# FeatherBigLatchingRelay.net
KiCad netlist of a schematic drawn in EAGLE
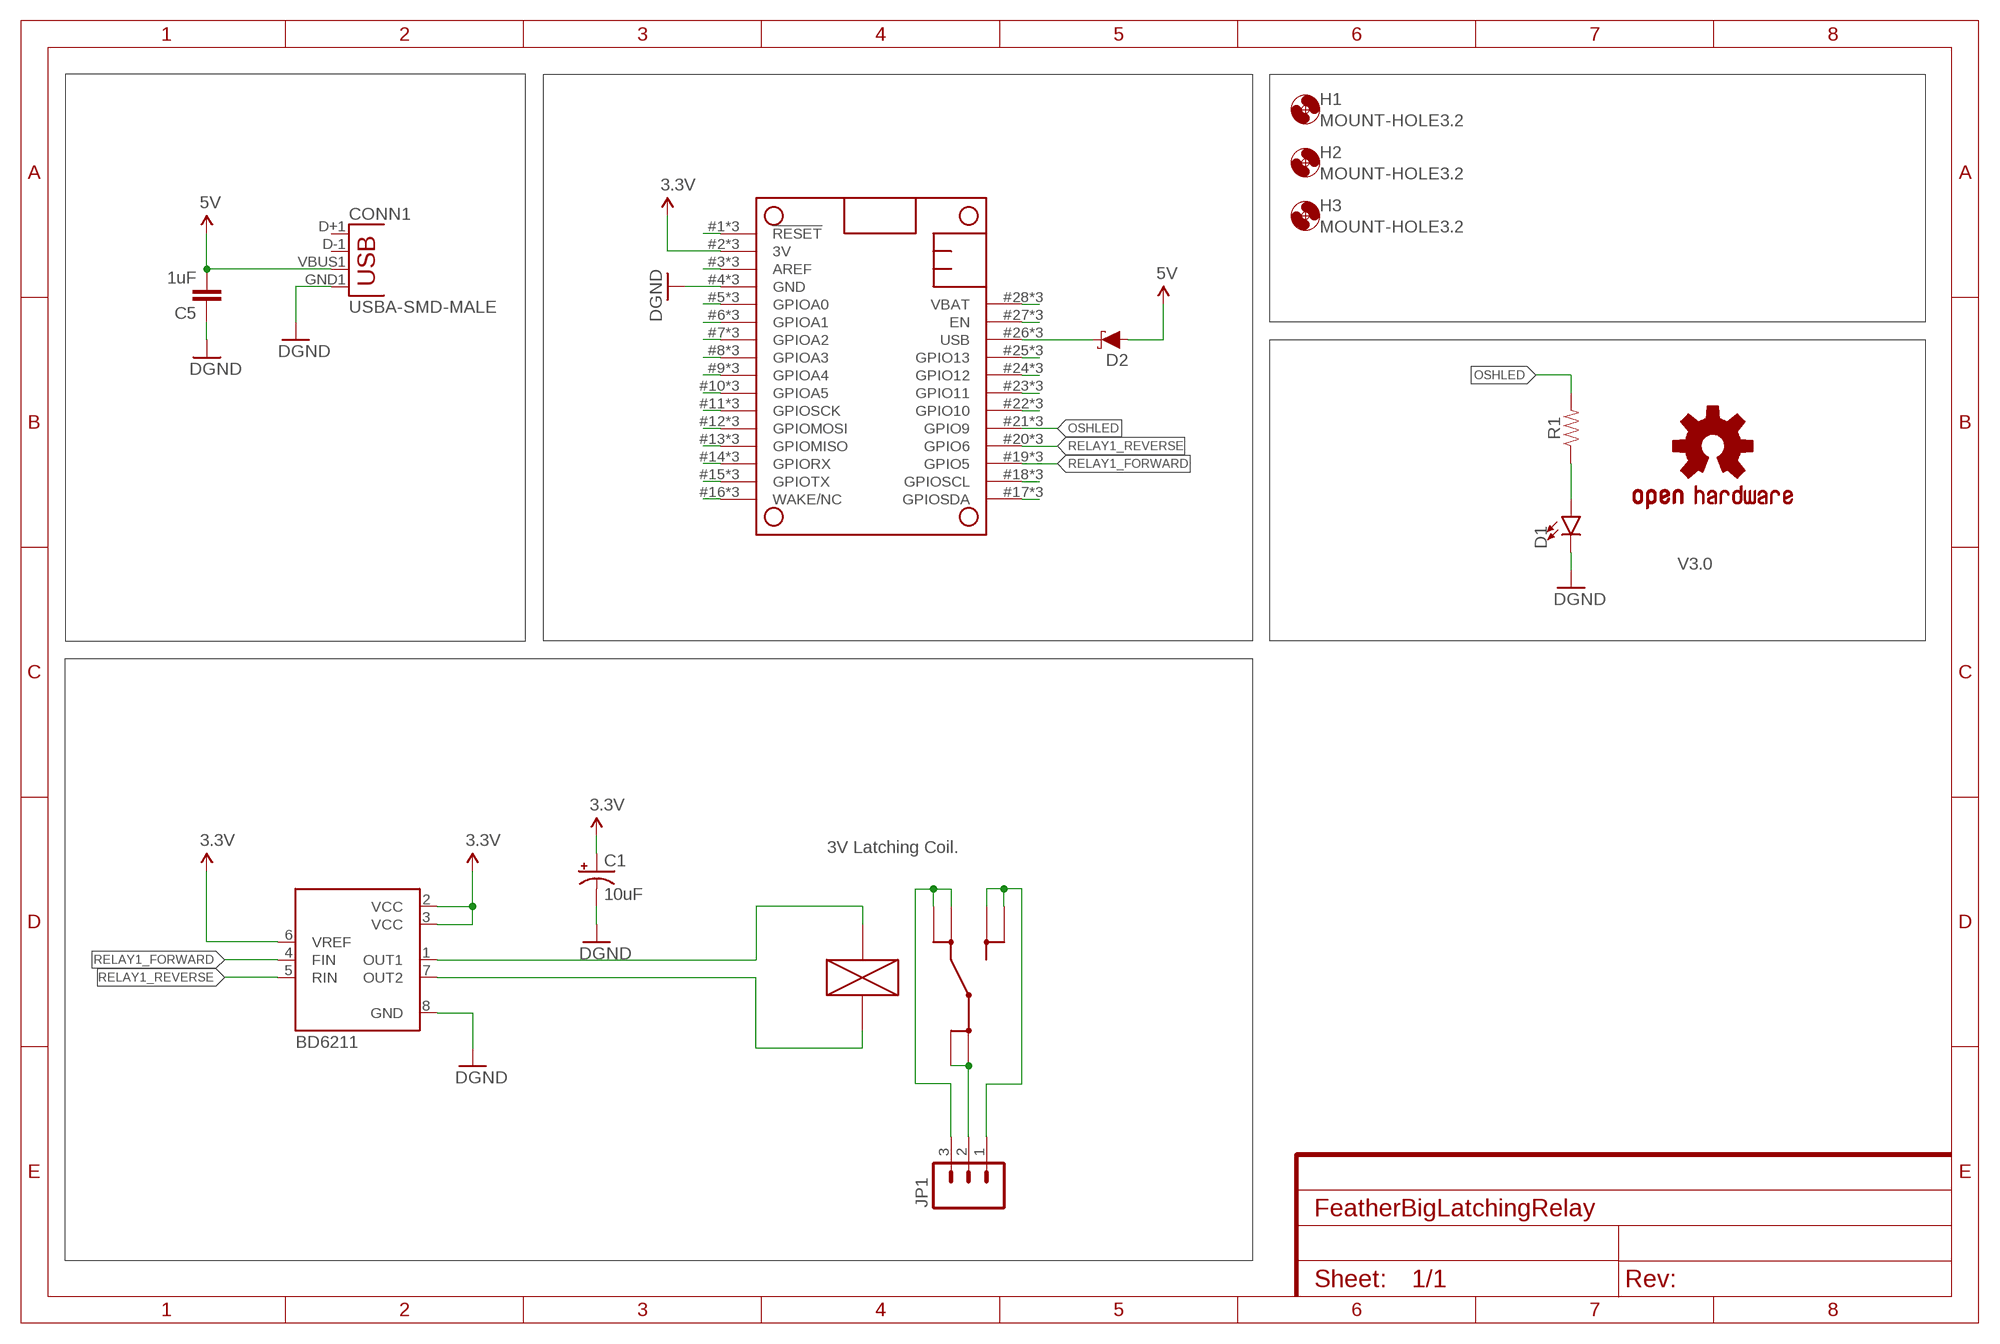
[diagram p0: schematic, sheet 1]

(export (version "E")
  (design (tool "Eeschema 10.0.6"))
  (components
    (comp (ref "C1")
      (value "10uF")
      (footprint "eagle-import:EIA3216")
      (libsource (lib "eagle-import") (part "10UF-16V-10%(TANT)"))
    )
    (comp (ref "C5")
      (value "1uF")
      (footprint "eagle-import:0805")
      (libsource (lib "eagle-import") (part "CAP0805"))
    )
    (comp (ref "CONN1")
      (value "USBA-SMD-MALE")
      (footprint "eagle-import:USB-A-SMT-MALE")
      (libsource (lib "eagle-import") (part "USBA-SMD-MALE"))
    )
    (comp (ref "D1")
      (value "LED1206-BOTTOM")
      (footprint "eagle-import:LED-1206-BOTTOM")
      (libsource (lib "eagle-import") (part "LED1206-BOTTOM"))
    )
    (comp (ref "D2")
      (value "3A/40V/500mV")
      (footprint "eagle-import:SMA-DIODE")
      (libsource (lib "eagle-import") (part "DIODE-SCHOTTKY-B340A"))
    )
    (comp (ref "H1")
      (value "MOUNT-HOLE3.2")
      (footprint "eagle-import:3,2")
      (libsource (lib "eagle-import") (part "MOUNT-HOLE3.2"))
    )
    (comp (ref "H2")
      (value "MOUNT-HOLE3.2")
      (footprint "eagle-import:3,2")
      (libsource (lib "eagle-import") (part "MOUNT-HOLE3.2"))
    )
    (comp (ref "H3")
      (value "MOUNT-HOLE3.2")
      (footprint "eagle-import:3,2")
      (libsource (lib "eagle-import") (part "MOUNT-HOLE3.2"))
    )
    (comp (ref "JP1")
      (value "M03-SCREW-5MM")
      (footprint "eagle-import:SCREWTERMINAL-5MM-3")
      (libsource (lib "eagle-import") (part "M03-SCREW-5MM"))
    )
    (comp (ref "LOGO1")
      (value "OSHW-LOGOM")
      (footprint "eagle-import:OSHW-LOGO-M")
      (libsource (lib "eagle-import") (part "OSHW-LOGOM"))
    )
    (comp (ref "MS1")
      (value "FEATHERWINGFEATHERWING_BREAKOUT_INSIDEONLY")
      (footprint "eagle-import:FEATHERWING_BREAKOUT_INSIDE_ONLY")
      (libsource (lib "eagle-import") (part "FEATHERWINGFEATHERWING_BREAKOUT_INSIDEONLY"))
    )
    (comp (ref "R1")
      (value "RESISTOR1206")
      (footprint "eagle-import:1206")
      (libsource (lib "eagle-import") (part "RESISTOR1206"))
    )
    (comp (ref "U$1")
      (value "RELAY_G5RL-1E")
      (footprint "eagle-import:G5RL-1E")
      (libsource (lib "eagle-import") (part "RELAY_G5RL-1E"))
    )
    (comp (ref "U3")
      (value "BD6211F")
      (footprint "eagle-import:SOP8")
      (libsource (lib "eagle-import") (part "BD6211F"))
    )
  )
  (nets
    (net (code "1") (name "3.3V") (class "Default")
      (node (ref "C1") (pin "A") (pinfunction "+_A") (pintype "passive"))
      (node (ref "MS1") (pin "#2") (pinfunction "3V_#2") (pintype "power_in"))
      (node (ref "MS1") (pin "2") (pinfunction "3V_2") (pintype "power_in"))
      (node (ref "MS1") (pin "@2") (pinfunction "3V_@2") (pintype "power_in"))
      (node (ref "U3") (pin "2") (pinfunction "VCC_2") (pintype "power_in"))
      (node (ref "U3") (pin "3") (pinfunction "VCC_3") (pintype "power_in"))
      (node (ref "U3") (pin "6") (pinfunction "VREF_6") (pintype "passive"))
    )
    (net (code "2") (name "5V") (class "Default")
      (node (ref "C5") (pin "2") (pinfunction "2_2") (pintype "passive"))
      (node (ref "CONN1") (pin "VBUS1") (pinfunction "VBUS_VBUS1") (pintype "bidirectional"))
      (node (ref "D2") (pin "A") (pinfunction "A_A") (pintype "passive"))
    )
    (net (code "3") (name "DGND") (class "Default")
      (node (ref "C1") (pin "C") (pinfunction "-_C") (pintype "passive"))
      (node (ref "C5") (pin "1") (pinfunction "1_1") (pintype "passive"))
      (node (ref "CONN1") (pin "GND1") (pinfunction "GND_GND1") (pintype "bidirectional"))
      (node (ref "D1") (pin "C") (pinfunction "C_C") (pintype "passive"))
      (node (ref "MS1") (pin "#4") (pinfunction "GND_#4") (pintype "power_in"))
      (node (ref "MS1") (pin "4") (pinfunction "GND_4") (pintype "power_in"))
      (node (ref "MS1") (pin "@4") (pinfunction "GND_@4") (pintype "power_in"))
      (node (ref "U3") (pin "8") (pinfunction "GND_8") (pintype "power_in"))
    )
    (net (code "4") (name "Net-(D1-PadA)") (class "Default")
      (node (ref "D1") (pin "A") (pinfunction "A_A") (pintype "passive"))
      (node (ref "R1") (pin "1") (pinfunction "1_1") (pintype "passive"))
    )
    (net (code "5") (name "Net-(D2-PadC)") (class "Default")
      (node (ref "D2") (pin "C") (pinfunction "C_C") (pintype "passive"))
      (node (ref "MS1") (pin "#26") (pinfunction "USB_#26") (pintype "power_in"))
      (node (ref "MS1") (pin "26") (pinfunction "USB_26") (pintype "power_in"))
      (node (ref "MS1") (pin "@26") (pinfunction "USB_@26") (pintype "power_in"))
    )
    (net (code "6") (name "Net-(JP1-Pad1)") (class "Default")
      (node (ref "JP1") (pin "1") (pinfunction "1_1") (pintype "passive"))
      (node (ref "U$1") (pin "NO@1") (pinfunction "NO_NO@1") (pintype "bidirectional"))
      (node (ref "U$1") (pin "NO@2") (pinfunction "NO_NO@2") (pintype "bidirectional"))
    )
    (net (code "7") (name "Net-(JP1-Pad2)") (class "Default")
      (node (ref "JP1") (pin "2") (pinfunction "2_2") (pintype "passive"))
      (node (ref "U$1") (pin "COM@1") (pinfunction "COM_COM@1") (pintype "bidirectional"))
      (node (ref "U$1") (pin "COM@2") (pinfunction "COM_COM@2") (pintype "bidirectional"))
    )
    (net (code "8") (name "Net-(JP1-Pad3)") (class "Default")
      (node (ref "JP1") (pin "3") (pinfunction "3_3") (pintype "passive"))
      (node (ref "U$1") (pin "NC@1") (pinfunction "NC_NC@1") (pintype "bidirectional"))
      (node (ref "U$1") (pin "NC@2") (pinfunction "NC_NC@2") (pintype "bidirectional"))
    )
    (net (code "9") (name "Net-(MS1-AREF-Pad#3)") (class "Default")
      (node (ref "MS1") (pin "#3") (pinfunction "AREF_#3") (pintype "passive"))
      (node (ref "MS1") (pin "3") (pinfunction "AREF_3") (pintype "passive"))
      (node (ref "MS1") (pin "@3") (pinfunction "AREF_@3") (pintype "passive"))
    )
    (net (code "10") (name "Net-(MS1-EN-Pad#27)") (class "Default")
      (node (ref "MS1") (pin "#27") (pinfunction "EN_#27") (pintype "passive"))
      (node (ref "MS1") (pin "27") (pinfunction "EN_27") (pintype "passive"))
      (node (ref "MS1") (pin "@27") (pinfunction "EN_@27") (pintype "passive"))
    )
    (net (code "11") (name "Net-(MS1-GPIO10-Pad#22)") (class "Default")
      (node (ref "MS1") (pin "#22") (pinfunction "GPIO10_#22") (pintype "bidirectional"))
      (node (ref "MS1") (pin "22") (pinfunction "GPIO10_22") (pintype "bidirectional"))
      (node (ref "MS1") (pin "@22") (pinfunction "GPIO10_@22") (pintype "bidirectional"))
    )
    (net (code "12") (name "Net-(MS1-GPIO11-Pad#23)") (class "Default")
      (node (ref "MS1") (pin "#23") (pinfunction "GPIO11_#23") (pintype "bidirectional"))
      (node (ref "MS1") (pin "23") (pinfunction "GPIO11_23") (pintype "bidirectional"))
      (node (ref "MS1") (pin "@23") (pinfunction "GPIO11_@23") (pintype "bidirectional"))
    )
    (net (code "13") (name "Net-(MS1-GPIO12-Pad#24)") (class "Default")
      (node (ref "MS1") (pin "#24") (pinfunction "GPIO12_#24") (pintype "bidirectional"))
      (node (ref "MS1") (pin "24") (pinfunction "GPIO12_24") (pintype "bidirectional"))
      (node (ref "MS1") (pin "@24") (pinfunction "GPIO12_@24") (pintype "bidirectional"))
    )
    (net (code "14") (name "Net-(MS1-GPIO13-Pad#25)") (class "Default")
      (node (ref "MS1") (pin "#25") (pinfunction "GPIO13_#25") (pintype "bidirectional"))
      (node (ref "MS1") (pin "25") (pinfunction "GPIO13_25") (pintype "bidirectional"))
      (node (ref "MS1") (pin "@25") (pinfunction "GPIO13_@25") (pintype "bidirectional"))
    )
    (net (code "15") (name "Net-(MS1-GPIOA0-Pad#5)") (class "Default")
      (node (ref "MS1") (pin "#5") (pinfunction "GPIOA0_#5") (pintype "bidirectional"))
      (node (ref "MS1") (pin "5") (pinfunction "GPIOA0_5") (pintype "bidirectional"))
      (node (ref "MS1") (pin "@5") (pinfunction "GPIOA0_@5") (pintype "bidirectional"))
    )
    (net (code "16") (name "Net-(MS1-GPIOA1-Pad#6)") (class "Default")
      (node (ref "MS1") (pin "#6") (pinfunction "GPIOA1_#6") (pintype "bidirectional"))
      (node (ref "MS1") (pin "6") (pinfunction "GPIOA1_6") (pintype "bidirectional"))
      (node (ref "MS1") (pin "@6") (pinfunction "GPIOA1_@6") (pintype "bidirectional"))
    )
    (net (code "17") (name "Net-(MS1-GPIOA2-Pad#7)") (class "Default")
      (node (ref "MS1") (pin "#7") (pinfunction "GPIOA2_#7") (pintype "bidirectional"))
      (node (ref "MS1") (pin "7") (pinfunction "GPIOA2_7") (pintype "bidirectional"))
      (node (ref "MS1") (pin "@7") (pinfunction "GPIOA2_@7") (pintype "bidirectional"))
    )
    (net (code "18") (name "Net-(MS1-GPIOA3-Pad#8)") (class "Default")
      (node (ref "MS1") (pin "#8") (pinfunction "GPIOA3_#8") (pintype "bidirectional"))
      (node (ref "MS1") (pin "8") (pinfunction "GPIOA3_8") (pintype "bidirectional"))
      (node (ref "MS1") (pin "@8") (pinfunction "GPIOA3_@8") (pintype "bidirectional"))
    )
    (net (code "19") (name "Net-(MS1-GPIOA4-Pad#9)") (class "Default")
      (node (ref "MS1") (pin "#9") (pinfunction "GPIOA4_#9") (pintype "bidirectional"))
      (node (ref "MS1") (pin "9") (pinfunction "GPIOA4_9") (pintype "bidirectional"))
      (node (ref "MS1") (pin "@9") (pinfunction "GPIOA4_@9") (pintype "bidirectional"))
    )
    (net (code "20") (name "Net-(MS1-GPIOA5-Pad#10)") (class "Default")
      (node (ref "MS1") (pin "#10") (pinfunction "GPIOA5_#10") (pintype "bidirectional"))
      (node (ref "MS1") (pin "10") (pinfunction "GPIOA5_10") (pintype "bidirectional"))
      (node (ref "MS1") (pin "@10") (pinfunction "GPIOA5_@10") (pintype "bidirectional"))
    )
    (net (code "21") (name "Net-(MS1-GPIOMISO-Pad#13)") (class "Default")
      (node (ref "MS1") (pin "#13") (pinfunction "GPIOMISO_#13") (pintype "bidirectional"))
      (node (ref "MS1") (pin "13") (pinfunction "GPIOMISO_13") (pintype "bidirectional"))
      (node (ref "MS1") (pin "@13") (pinfunction "GPIOMISO_@13") (pintype "bidirectional"))
    )
    (net (code "22") (name "Net-(MS1-GPIOMOSI-Pad#12)") (class "Default")
      (node (ref "MS1") (pin "#12") (pinfunction "GPIOMOSI_#12") (pintype "bidirectional"))
      (node (ref "MS1") (pin "12") (pinfunction "GPIOMOSI_12") (pintype "bidirectional"))
      (node (ref "MS1") (pin "@12") (pinfunction "GPIOMOSI_@12") (pintype "bidirectional"))
    )
    (net (code "23") (name "Net-(MS1-GPIORX-Pad#14)") (class "Default")
      (node (ref "MS1") (pin "#14") (pinfunction "GPIORX_#14") (pintype "bidirectional"))
      (node (ref "MS1") (pin "14") (pinfunction "GPIORX_14") (pintype "bidirectional"))
      (node (ref "MS1") (pin "@14") (pinfunction "GPIORX_@14") (pintype "bidirectional"))
    )
    (net (code "24") (name "Net-(MS1-GPIOSCK-Pad#11)") (class "Default")
      (node (ref "MS1") (pin "#11") (pinfunction "GPIOSCK_#11") (pintype "bidirectional"))
      (node (ref "MS1") (pin "11") (pinfunction "GPIOSCK_11") (pintype "bidirectional"))
      (node (ref "MS1") (pin "@11") (pinfunction "GPIOSCK_@11") (pintype "bidirectional"))
    )
    (net (code "25") (name "Net-(MS1-GPIOSCL-Pad#18)") (class "Default")
      (node (ref "MS1") (pin "#18") (pinfunction "GPIOSCL_#18") (pintype "bidirectional"))
      (node (ref "MS1") (pin "18") (pinfunction "GPIOSCL_18") (pintype "bidirectional"))
      (node (ref "MS1") (pin "@!8") (pinfunction "GPIOSCL_@!8") (pintype "bidirectional"))
    )
    (net (code "26") (name "Net-(MS1-GPIOSDA-Pad#17)") (class "Default")
      (node (ref "MS1") (pin "#17") (pinfunction "GPIOSDA_#17") (pintype "bidirectional"))
      (node (ref "MS1") (pin "17") (pinfunction "GPIOSDA_17") (pintype "bidirectional"))
      (node (ref "MS1") (pin "@17") (pinfunction "GPIOSDA_@17") (pintype "bidirectional"))
    )
    (net (code "27") (name "Net-(MS1-GPIOTX-Pad#15)") (class "Default")
      (node (ref "MS1") (pin "#15") (pinfunction "GPIOTX_#15") (pintype "bidirectional"))
      (node (ref "MS1") (pin "15") (pinfunction "GPIOTX_15") (pintype "bidirectional"))
      (node (ref "MS1") (pin "@15") (pinfunction "GPIOTX_@15") (pintype "bidirectional"))
    )
    (net (code "28") (name "Net-(MS1-VBAT-Pad#28)") (class "Default")
      (node (ref "MS1") (pin "#28") (pinfunction "VBAT_#28") (pintype "power_in"))
      (node (ref "MS1") (pin "28") (pinfunction "VBAT_28") (pintype "power_in"))
      (node (ref "MS1") (pin "@28") (pinfunction "VBAT_@28") (pintype "power_in"))
    )
    (net (code "29") (name "Net-(MS1-WAKE{slash}NC-Pad#16)") (class "Default")
      (node (ref "MS1") (pin "#16") (pinfunction "WAKE/NC_#16") (pintype "passive"))
      (node (ref "MS1") (pin "16") (pinfunction "WAKE/NC_16") (pintype "passive"))
      (node (ref "MS1") (pin "@16") (pinfunction "WAKE/NC_@16") (pintype "passive"))
    )
    (net (code "30") (name "Net-(MS1-~{RESET}-Pad#1)") (class "Default")
      (node (ref "MS1") (pin "#1") (pinfunction "~{RESET}_#1") (pintype "input"))
      (node (ref "MS1") (pin "1") (pinfunction "~{RESET}_1") (pintype "input"))
      (node (ref "MS1") (pin "@1") (pinfunction "~{RESET}_@1") (pintype "input"))
    )
    (net (code "31") (name "Net-(U3-OUT1)") (class "Default")
      (node (ref "U$1") (pin "COIL+") (pinfunction "COIL+_COIL+") (pintype "bidirectional"))
      (node (ref "U3") (pin "1") (pinfunction "OUT1_1") (pintype "output"))
    )
    (net (code "32") (name "Net-(U3-OUT2)") (class "Default")
      (node (ref "U$1") (pin "COIL-") (pinfunction "COIL-_COIL-") (pintype "bidirectional"))
      (node (ref "U3") (pin "7") (pinfunction "OUT2_7") (pintype "output"))
    )
    (net (code "33") (name "OSHLED") (class "Default")
      (node (ref "MS1") (pin "#21") (pinfunction "GPIO9_#21") (pintype "bidirectional"))
      (node (ref "MS1") (pin "21") (pinfunction "GPIO9_21") (pintype "bidirectional"))
      (node (ref "MS1") (pin "@21") (pinfunction "GPIO9_@21") (pintype "bidirectional"))
      (node (ref "R1") (pin "2") (pinfunction "2_2") (pintype "passive"))
    )
    (net (code "34") (name "RELAY1_FORWARD") (class "Default")
      (node (ref "MS1") (pin "#19") (pinfunction "GPIO5_#19") (pintype "bidirectional"))
      (node (ref "MS1") (pin "19") (pinfunction "GPIO5_19") (pintype "bidirectional"))
      (node (ref "MS1") (pin "@19") (pinfunction "GPIO5_@19") (pintype "bidirectional"))
      (node (ref "U3") (pin "4") (pinfunction "FIN_4") (pintype "input"))
    )
    (net (code "35") (name "RELAY1_REVERSE") (class "Default")
      (node (ref "MS1") (pin "#20") (pinfunction "GPIO6_#20") (pintype "bidirectional"))
      (node (ref "MS1") (pin "20") (pinfunction "GPIO6_20") (pintype "bidirectional"))
      (node (ref "MS1") (pin "@20") (pinfunction "GPIO6_@20") (pintype "bidirectional"))
      (node (ref "U3") (pin "5") (pinfunction "RIN_5") (pintype "input"))
    )
    (net (code "36") (name "unconnected-(CONN1-D+-PadD+1)") (class "Default")
      (node (ref "CONN1") (pin "D+1") (pinfunction "D+_D+1") (pintype "bidirectional"))
    )
    (net (code "37") (name "unconnected-(CONN1-D--PadD-1)") (class "Default")
      (node (ref "CONN1") (pin "D-1") (pinfunction "D-_D-1") (pintype "bidirectional"))
    )
  )
)
